# power_eagle_1.net
KiCad netlist of a schematic drawn in Altium Designer
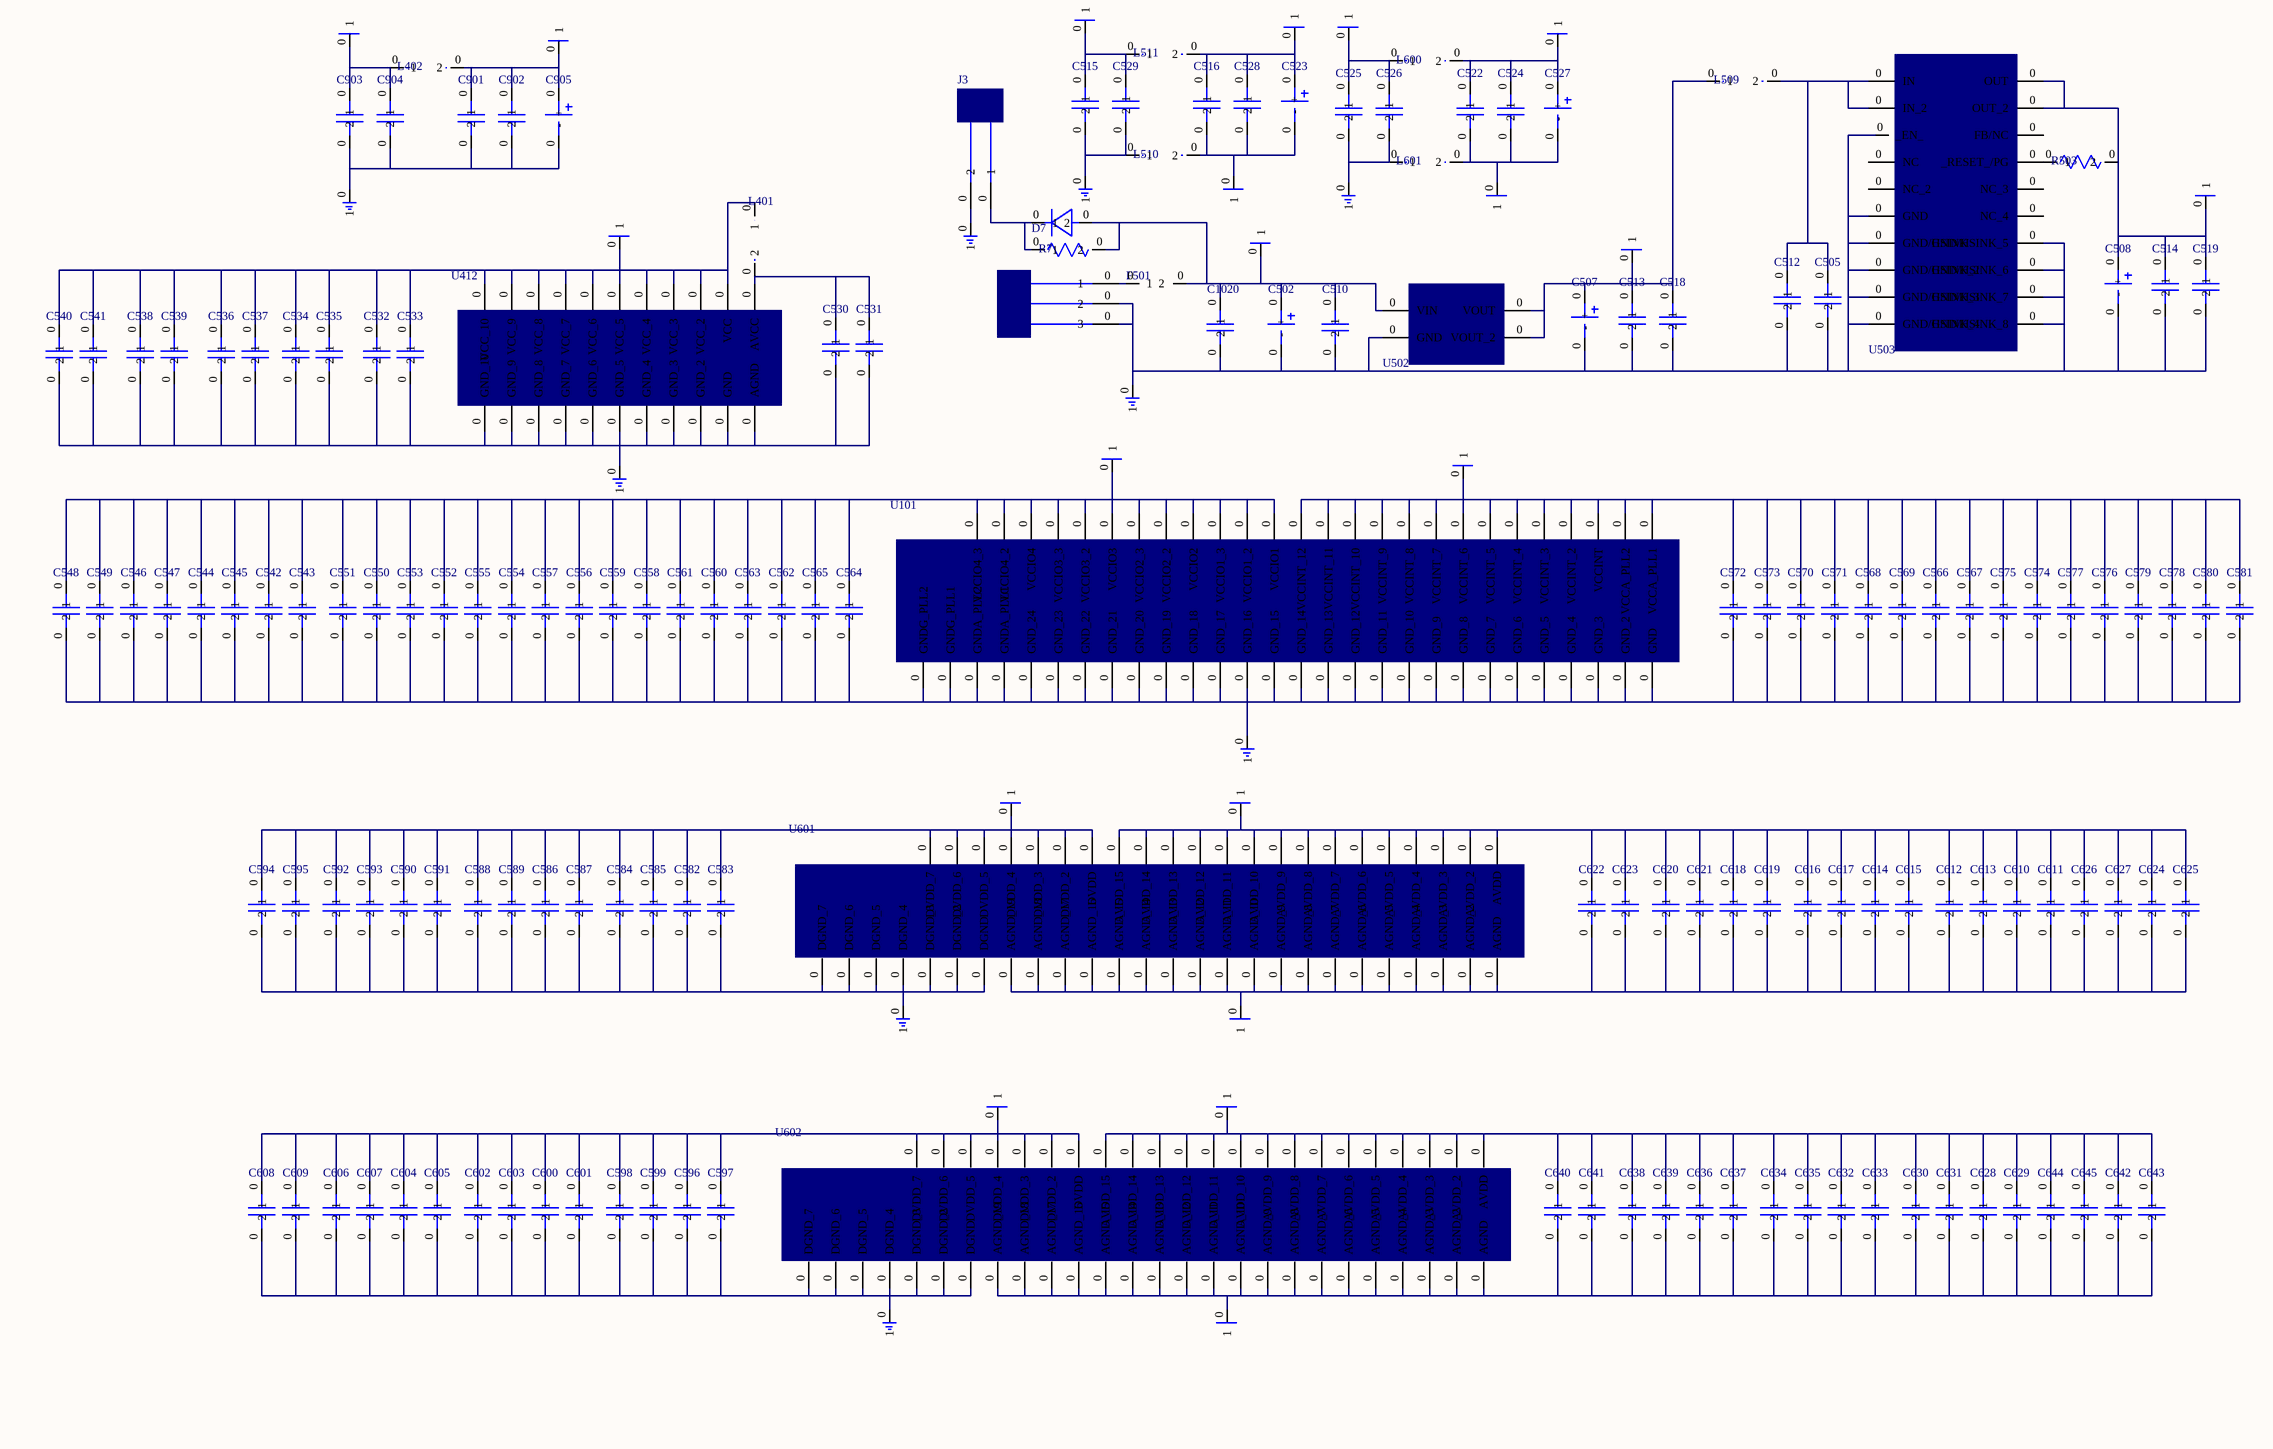
[diagram p0: power_eagle_1.SchDoc]

(export (version "E")
  (design (tool "Eeschema 10.0.6"))
  (components
    (comp (ref "C502") (value "~") (libsource (lib "") (part "CAPACITOR-2_5")))
    (comp (ref "C505") (value "~") (libsource (lib "") (part "CAPACITOR-1_84")))
    (comp (ref "C507") (value "~") (libsource (lib "") (part "CAPACITOR-2_4")))
    (comp (ref "C508") (value "~") (libsource (lib "") (part "CAPACITOR-2_3")))
    (comp (ref "C510") (value "~") (libsource (lib "") (part "CAPACITOR-1_63")))
    (comp (ref "C512") (value "~") (libsource (lib "") (part "CAPACITOR-1_24")))
    (comp (ref "C513") (value "~") (libsource (lib "") (part "CAPACITOR-1_2")))
    (comp (ref "C514") (value "~") (libsource (lib "") (part "CAPACITOR-1_52")))
    (comp (ref "C515") (value "~") (libsource (lib "") (part "CAPACITOR-1_101")))
    (comp (ref "C516") (value "~") (libsource (lib "") (part "CAPACITOR-1_31")))
    (comp (ref "C518") (value "~") (libsource (lib "") (part "CAPACITOR-1_33")))
    (comp (ref "C519") (value "~") (libsource (lib "") (part "CAPACITOR-1_108")))
    (comp (ref "C522") (value "~") (libsource (lib "") (part "CAPACITOR-1_9")))
    (comp (ref "C523") (value "~") (libsource (lib "openjson") (part "CAPACITOR-2")))
    (comp (ref "C524") (value "~") (libsource (lib "") (part "CAPACITOR-1_65")))
    (comp (ref "C525") (value "~") (libsource (lib "") (part "CAPACITOR-1_6")))
    (comp (ref "C526") (value "~") (libsource (lib "") (part "CAPACITOR-1_23")))
    (comp (ref "C527") (value "~") (libsource (lib "") (part "CAPACITOR-2_1")))
    (comp (ref "C528") (value "~") (libsource (lib "") (part "CAPACITOR-1_75")))
    (comp (ref "C529") (value "~") (libsource (lib "") (part "CAPACITOR-1_104")))
    (comp (ref "C530") (value "~") (libsource (lib "") (part "CAPACITOR-1_25")))
    (comp (ref "C531") (value "~") (libsource (lib "") (part "CAPACITOR-1_69")))
    (comp (ref "C532") (value "~") (libsource (lib "") (part "CAPACITOR-1_20")))
    (comp (ref "C533") (value "~") (libsource (lib "") (part "CAPACITOR-1_48")))
    (comp (ref "C534") (value "~") (libsource (lib "") (part "CAPACITOR-1_5")))
    (comp (ref "C535") (value "~") (libsource (lib "") (part "CAPACITOR-1_55")))
    (comp (ref "C536") (value "~") (libsource (lib "") (part "CAPACITOR-1_119")))
    (comp (ref "C537") (value "~") (libsource (lib "") (part "CAPACITOR-1_12")))
    (comp (ref "C538") (value "~") (libsource (lib "") (part "CAPACITOR-1_126")))
    (comp (ref "C539") (value "~") (libsource (lib "") (part "CAPACITOR-1_116")))
    (comp (ref "C540") (value "~") (libsource (lib "") (part "CAPACITOR-1_49")))
    (comp (ref "C541") (value "~") (libsource (lib "") (part "CAPACITOR-1_37")))
    (comp (ref "C542") (value "~") (libsource (lib "") (part "CAPACITOR-1_18")))
    (comp (ref "C543") (value "~") (libsource (lib "") (part "CAPACITOR-1_36")))
    (comp (ref "C544") (value "~") (libsource (lib "") (part "CAPACITOR-1_114")))
    (comp (ref "C545") (value "~") (libsource (lib "") (part "CAPACITOR-1_11")))
    (comp (ref "C546") (value "~") (libsource (lib "") (part "CAPACITOR-1_30")))
    (comp (ref "C547") (value "~") (libsource (lib "") (part "CAPACITOR-1_46")))
    (comp (ref "C548") (value "~") (libsource (lib "") (part "CAPACITOR-1_77")))
    (comp (ref "C549") (value "~") (libsource (lib "openjson") (part "CAPACITOR-1")))
    (comp (ref "C550") (value "~") (libsource (lib "") (part "CAPACITOR-1_62")))
    (comp (ref "C551") (value "~") (libsource (lib "") (part "CAPACITOR-1_68")))
    (comp (ref "C552") (value "~") (libsource (lib "") (part "CAPACITOR-1_56")))
    (comp (ref "C553") (value "~") (libsource (lib "") (part "CAPACITOR-1_38")))
    (comp (ref "C554") (value "~") (libsource (lib "") (part "CAPACITOR-1_3")))
    (comp (ref "C555") (value "~") (libsource (lib "") (part "CAPACITOR-1_35")))
    (comp (ref "C556") (value "~") (libsource (lib "") (part "CAPACITOR-1_100")))
    (comp (ref "C557") (value "~") (libsource (lib "") (part "CAPACITOR-1_39")))
    (comp (ref "C558") (value "~") (libsource (lib "") (part "CAPACITOR-1_113")))
    (comp (ref "C559") (value "~") (libsource (lib "") (part "CAPACITOR-1_15")))
    (comp (ref "C560") (value "~") (libsource (lib "") (part "CAPACITOR-1_121")))
    (comp (ref "C561") (value "~") (libsource (lib "") (part "CAPACITOR-1_81")))
    (comp (ref "C562") (value "~") (libsource (lib "") (part "CAPACITOR-1_72")))
    (comp (ref "C563") (value "~") (libsource (lib "") (part "CAPACITOR-1_134")))
    (comp (ref "C564") (value "~") (libsource (lib "") (part "CAPACITOR-1_40")))
    (comp (ref "C565") (value "~") (libsource (lib "") (part "CAPACITOR-1_27")))
    (comp (ref "C566") (value "~") (libsource (lib "") (part "CAPACITOR-1_32")))
    (comp (ref "C567") (value "~") (libsource (lib "") (part "CAPACITOR-1_127")))
    (comp (ref "C568") (value "~") (libsource (lib "") (part "CAPACITOR-1_79")))
    (comp (ref "C569") (value "~") (libsource (lib "") (part "CAPACITOR-1_13")))
    (comp (ref "C570") (value "~") (libsource (lib "") (part "CAPACITOR-1_91")))
    (comp (ref "C571") (value "~") (libsource (lib "") (part "CAPACITOR-1_21")))
    (comp (ref "C572") (value "~") (libsource (lib "") (part "CAPACITOR-1_45")))
    (comp (ref "C573") (value "~") (libsource (lib "") (part "CAPACITOR-1_53")))
    (comp (ref "C574") (value "~") (libsource (lib "") (part "CAPACITOR-1_132")))
    (comp (ref "C575") (value "~") (libsource (lib "") (part "CAPACITOR-1_7")))
    (comp (ref "C576") (value "~") (libsource (lib "") (part "CAPACITOR-1_64")))
    (comp (ref "C577") (value "~") (libsource (lib "") (part "CAPACITOR-1_42")))
    (comp (ref "C578") (value "~") (libsource (lib "") (part "CAPACITOR-1_125")))
    (comp (ref "C579") (value "~") (libsource (lib "") (part "CAPACITOR-1_123")))
    (comp (ref "C580") (value "~") (libsource (lib "") (part "CAPACITOR-1_58")))
    (comp (ref "C581") (value "~") (libsource (lib "") (part "CAPACITOR-1_26")))
    (comp (ref "C582") (value "~") (libsource (lib "") (part "CAPACITOR-1_1")))
    (comp (ref "C583") (value "~") (libsource (lib "") (part "CAPACITOR-1_83")))
    (comp (ref "C584") (value "~") (libsource (lib "") (part "CAPACITOR-1_51")))
    (comp (ref "C585") (value "~") (libsource (lib "") (part "CAPACITOR-1_57")))
    (comp (ref "C586") (value "~") (libsource (lib "") (part "CAPACITOR-1_131")))
    (comp (ref "C587") (value "~") (libsource (lib "") (part "CAPACITOR-1_105")))
    (comp (ref "C588") (value "~") (libsource (lib "") (part "CAPACITOR-1_115")))
    (comp (ref "C589") (value "~") (libsource (lib "") (part "CAPACITOR-1_130")))
    (comp (ref "C590") (value "~") (libsource (lib "") (part "CAPACITOR-1_120")))
    (comp (ref "C591") (value "~") (libsource (lib "") (part "CAPACITOR-1_86")))
    (comp (ref "C592") (value "~") (libsource (lib "") (part "CAPACITOR-1_112")))
    (comp (ref "C593") (value "~") (libsource (lib "") (part "CAPACITOR-1_22")))
    (comp (ref "C594") (value "~") (libsource (lib "") (part "CAPACITOR-1_67")))
    (comp (ref "C595") (value "~") (libsource (lib "") (part "CAPACITOR-1_133")))
    (comp (ref "C596") (value "~") (libsource (lib "") (part "CAPACITOR-1_80")))
    (comp (ref "C597") (value "~") (libsource (lib "") (part "CAPACITOR-1_28")))
    (comp (ref "C598") (value "~") (libsource (lib "") (part "CAPACITOR-1_118")))
    (comp (ref "C599") (value "~") (libsource (lib "") (part "CAPACITOR-1_54")))
    (comp (ref "C600") (value "~") (libsource (lib "") (part "CAPACITOR-1_66")))
    (comp (ref "C601") (value "~") (libsource (lib "") (part "CAPACITOR-1_76")))
    (comp (ref "C602") (value "~") (libsource (lib "") (part "CAPACITOR-1_74")))
    (comp (ref "C603") (value "~") (libsource (lib "") (part "CAPACITOR-1_89")))
    (comp (ref "C604") (value "~") (libsource (lib "") (part "CAPACITOR-1_90")))
    (comp (ref "C605") (value "~") (libsource (lib "") (part "CAPACITOR-1_59")))
    (comp (ref "C606") (value "~") (libsource (lib "") (part "CAPACITOR-1_117")))
    (comp (ref "C607") (value "~") (libsource (lib "") (part "CAPACITOR-1_34")))
    (comp (ref "C608") (value "~") (libsource (lib "") (part "CAPACITOR-1_71")))
    (comp (ref "C609") (value "~") (libsource (lib "") (part "CAPACITOR-1_88")))
    (comp (ref "C610") (value "~") (libsource (lib "") (part "CAPACITOR-1_17")))
    (comp (ref "C611") (value "~") (libsource (lib "") (part "CAPACITOR-1_16")))
    (comp (ref "C612") (value "~") (libsource (lib "") (part "CAPACITOR-1_19")))
    (comp (ref "C613") (value "~") (libsource (lib "") (part "CAPACITOR-1_44")))
    (comp (ref "C614") (value "~") (libsource (lib "") (part "CAPACITOR-1_103")))
    (comp (ref "C615") (value "~") (libsource (lib "") (part "CAPACITOR-1_110")))
    (comp (ref "C616") (value "~") (libsource (lib "") (part "CAPACITOR-1_97")))
    (comp (ref "C617") (value "~") (libsource (lib "") (part "CAPACITOR-1_73")))
    (comp (ref "C618") (value "~") (libsource (lib "") (part "CAPACITOR-1_96")))
    (comp (ref "C619") (value "~") (libsource (lib "") (part "CAPACITOR-1_41")))
    (comp (ref "C620") (value "~") (libsource (lib "") (part "CAPACITOR-1_128")))
    (comp (ref "C621") (value "~") (libsource (lib "") (part "CAPACITOR-1_61")))
    (comp (ref "C622") (value "~") (libsource (lib "") (part "CAPACITOR-1_10")))
    (comp (ref "C623") (value "~") (libsource (lib "") (part "CAPACITOR-1_50")))
    (comp (ref "C624") (value "~") (libsource (lib "") (part "CAPACITOR-1_85")))
    (comp (ref "C625") (value "~") (libsource (lib "") (part "CAPACITOR-1_43")))
    (comp (ref "C626") (value "~") (libsource (lib "") (part "CAPACITOR-1_47")))
    (comp (ref "C627") (value "~") (libsource (lib "") (part "CAPACITOR-1_99")))
    (comp (ref "C628") (value "~") (libsource (lib "") (part "CAPACITOR-1_94")))
    (comp (ref "C629") (value "~") (libsource (lib "") (part "CAPACITOR-1_78")))
    (comp (ref "C630") (value "~") (libsource (lib "") (part "CAPACITOR-1_129")))
    (comp (ref "C631") (value "~") (libsource (lib "") (part "CAPACITOR-1_111")))
    (comp (ref "C632") (value "~") (libsource (lib "") (part "CAPACITOR-1_109")))
    (comp (ref "C633") (value "~") (libsource (lib "") (part "CAPACITOR-1_60")))
    (comp (ref "C634") (value "~") (libsource (lib "") (part "CAPACITOR-1_14")))
    (comp (ref "C635") (value "~") (libsource (lib "") (part "CAPACITOR-1_8")))
    (comp (ref "C636") (value "~") (libsource (lib "") (part "CAPACITOR-1_135")))
    (comp (ref "C637") (value "~") (libsource (lib "") (part "CAPACITOR-1_93")))
    (comp (ref "C638") (value "~") (libsource (lib "") (part "CAPACITOR-1_122")))
    (comp (ref "C639") (value "~") (libsource (lib "") (part "CAPACITOR-1_82")))
    (comp (ref "C640") (value "~") (libsource (lib "") (part "CAPACITOR-1_4")))
    (comp (ref "C641") (value "~") (libsource (lib "") (part "CAPACITOR-1_107")))
    (comp (ref "C642") (value "~") (libsource (lib "") (part "CAPACITOR-1_102")))
    (comp (ref "C643") (value "~") (libsource (lib "") (part "CAPACITOR-1_95")))
    (comp (ref "C644") (value "~") (libsource (lib "") (part "CAPACITOR-1_92")))
    (comp (ref "C645") (value "~") (libsource (lib "") (part "CAPACITOR-1_70")))
    (comp (ref "C901") (value "~") (libsource (lib "") (part "CAPACITOR-1_87")))
    (comp (ref "C902") (value "~") (libsource (lib "") (part "CAPACITOR-1_29")))
    (comp (ref "C903") (value "~") (libsource (lib "") (part "CAPACITOR-1_106")))
    (comp (ref "C904") (value "~") (libsource (lib "") (part "CAPACITOR-1_124")))
    (comp (ref "C905") (value "~") (libsource (lib "") (part "CAPACITOR-2_2")))
    (comp (ref "C1020") (value "~") (libsource (lib "") (part "CAPACITOR-1_98")))
    (comp (ref "D7") (value "~") (libsource (lib "openjson") (part "DIODE-3")))
    (comp (ref "F501") (value "~") (libsource (lib "openjson") (part "FUSE-1")))
    (comp (ref "GENERIC-POWER") (value "~") (libsource (lib "openjson") (part "GENERIC-POWER")))
    (comp (ref "GENERIC-POWER-0") (value "~") (libsource (lib "openjson") (part "GENERIC-POWER")))
    (comp (ref "GENERIC-POWER-1") (value "~") (libsource (lib "openjson") (part "GENERIC-POWER")))
    (comp (ref "GENERIC-POWER-2") (value "~") (libsource (lib "openjson") (part "GENERIC-POWER")))
    (comp (ref "GENERIC-POWER-3") (value "~") (libsource (lib "openjson") (part "GENERIC-POWER")))
    (comp (ref "GENERIC-POWER-4") (value "~") (libsource (lib "") (part "GENERIC-POWER_1")))
    (comp (ref "GENERIC-POWER-6") (value "~") (libsource (lib "openjson") (part "GENERIC-POWER")))
    (comp (ref "GENERIC-POWER-7") (value "~") (libsource (lib "openjson") (part "GENERIC-POWER")))
    (comp (ref "GENERIC-POWER-8") (value "~") (libsource (lib "") (part "GENERIC-POWER_1")))
    (comp (ref "GENERIC-POWER-11") (value "~") (libsource (lib "openjson") (part "GENERIC-POWER")))
    (comp (ref "GENERIC-POWER-12") (value "~") (libsource (lib "openjson") (part "GENERIC-POWER")))
    (comp (ref "GENERIC-POWER-14") (value "~") (libsource (lib "openjson") (part "GENERIC-POWER")))
    (comp (ref "GENERIC-POWER-16") (value "~") (libsource (lib "openjson") (part "GENERIC-POWER")))
    (comp (ref "GENERIC-POWER-17") (value "~") (libsource (lib "openjson") (part "GENERIC-POWER")))
    (comp (ref "GENERIC-POWER-18") (value "~") (libsource (lib "") (part "GENERIC-POWER_1")))
    (comp (ref "GENERIC-POWER-20") (value "~") (libsource (lib "openjson") (part "GENERIC-POWER")))
    (comp (ref "GENERIC-POWER-21") (value "~") (libsource (lib "openjson") (part "GENERIC-POWER")))
    (comp (ref "GENERIC-POWER-22") (value "~") (libsource (lib "") (part "GENERIC-POWER_1")))
    (comp (ref "GENERIC-POWER-23") (value "~") (libsource (lib "openjson") (part "GENERIC-POWER")))
    (comp (ref "GENERIC-POWER-24") (value "~") (libsource (lib "openjson") (part "GENERIC-POWER")))
    (comp (ref "GND-1") (value "~") (libsource (lib "openjson") (part "GND-1")))
    (comp (ref "GND-1-5") (value "~") (libsource (lib "openjson") (part "GND-1")))
    (comp (ref "GND-1-9") (value "~") (libsource (lib "openjson") (part "GND-1")))
    (comp (ref "GND-1-10") (value "~") (libsource (lib "openjson") (part "GND-1")))
    (comp (ref "GND-1-13") (value "~") (libsource (lib "openjson") (part "GND-1")))
    (comp (ref "GND-1-15") (value "~") (libsource (lib "openjson") (part "GND-1")))
    (comp (ref "GND-1-19") (value "~") (libsource (lib "openjson") (part "GND-1")))
    (comp (ref "GND-1-25") (value "~") (libsource (lib "openjson") (part "GND-1")))
    (comp (ref "GND-1-26") (value "~") (libsource (lib "openjson") (part "GND-1")))
    (comp (ref "J3") (value "~") (libsource (lib "openjson") (part "CONNECTOR2-1")))
    (comp (ref "J502") (value "~") (libsource (lib "openjson") (part "CONNECTOR3-1")))
    (comp (ref "L401") (value "~") (libsource (lib "") (part "INDUCTOR-1_3")))
    (comp (ref "L402") (value "~") (libsource (lib "") (part "INDUCTOR-1_1")))
    (comp (ref "L509") (value "~") (libsource (lib "") (part "INDUCTOR-1_4")))
    (comp (ref "L510") (value "~") (libsource (lib "") (part "INDUCTOR-1_6")))
    (comp (ref "L511") (value "~") (libsource (lib "") (part "INDUCTOR-1_5")))
    (comp (ref "L600") (value "~") (libsource (lib "openjson") (part "INDUCTOR-1")))
    (comp (ref "L601") (value "~") (libsource (lib "") (part "INDUCTOR-1_2")))
    (comp (ref "R7") (value "~") (libsource (lib "") (part "RESISTOR-1_1")))
    (comp (ref "R503") (value "~") (libsource (lib "openjson") (part "RESISTOR-1")))
    (comp (ref "U101") (value "~") (libsource (lib "openjson") (part "EP1C12-PQ240-PWR")))
    (comp (ref "U412") (value "~") (libsource (lib "openjson") (part "CY7C68013-TQ100-PWR")))
    (comp (ref "U502") (value "~") (libsource (lib "openjson") (part "LT1085")))
    (comp (ref "U503") (value "~") (libsource (lib "openjson") (part "TPS777XX-PWP")))
    (comp (ref "U601") (value "~") (libsource (lib "") (part "AD986X-PWR_1")))
    (comp (ref "U602") (value "~") (libsource (lib "openjson") (part "AD986X-PWR")))
  )
  (nets
    (net (code "1") (name "Net-(C505-1)") (class "Default")
      (node (ref "C505") (pin "0") (pinfunction "1_0") (pintype "passive"))
      (node (ref "C512") (pin "0") (pinfunction "1_0") (pintype "passive"))
      (node (ref "L509") (pin "0") (pinfunction "2_0") (pintype "passive"))
      (node (ref "U503") (pin "0") (pinfunction "IN_0") (pintype "passive"))
    )
    (net (code "2") (name "Net-(C507-+)") (class "Default")
      (node (ref "C507") (pin "0") (pinfunction "+_0") (pintype "passive"))
      (node (ref "C513") (pin "0") (pinfunction "1_0") (pintype "passive"))
      (node (ref "C518") (pin "0") (pinfunction "1_0") (pintype "passive"))
      (node (ref "GENERIC-POWER-1") (pin "0") (pinfunction "1_0") (pintype "passive"))
      (node (ref "L509") (pin "0") (pinfunction "1_0") (pintype "passive"))
      (node (ref "U502") (pin "0") (pinfunction "VOUT_0") (pintype "passive"))
    )
    (net (code "3") (name "Net-(C508-+)") (class "Default")
      (node (ref "C508") (pin "0") (pinfunction "+_0") (pintype "passive"))
      (node (ref "C514") (pin "0") (pinfunction "1_0") (pintype "passive"))
      (node (ref "C519") (pin "0") (pinfunction "1_0") (pintype "passive"))
      (node (ref "GENERIC-POWER") (pin "0") (pinfunction "1_0") (pintype "passive"))
      (node (ref "R503") (pin "0") (pinfunction "2_0") (pintype "passive"))
      (node (ref "U503") (pin "0") (pinfunction "OUT_0") (pintype "passive"))
    )
    (net (code "4") (name "Net-(C515-1)") (class "Default")
      (node (ref "C515") (pin "0") (pinfunction "1_0") (pintype "passive"))
      (node (ref "C529") (pin "0") (pinfunction "1_0") (pintype "passive"))
      (node (ref "GENERIC-POWER-6") (pin "0") (pinfunction "1_0") (pintype "passive"))
      (node (ref "L511") (pin "0") (pinfunction "1_0") (pintype "passive"))
    )
    (net (code "5") (name "Net-(C515-2)") (class "Default")
      (node (ref "C515") (pin "0") (pinfunction "2_0") (pintype "passive"))
      (node (ref "C529") (pin "0") (pinfunction "2_0") (pintype "passive"))
      (node (ref "GND-1-9") (pin "0") (pinfunction "1_0") (pintype "passive"))
      (node (ref "L510") (pin "0") (pinfunction "1_0") (pintype "passive"))
    )
    (net (code "6") (name "Net-(C516-1)") (class "Default")
      (node (ref "C516") (pin "0") (pinfunction "1_0") (pintype "passive"))
      (node (ref "C523") (pin "0") (pinfunction "+_0") (pintype "passive"))
      (node (ref "C528") (pin "0") (pinfunction "1_0") (pintype "passive"))
      (node (ref "GENERIC-POWER-7") (pin "0") (pinfunction "1_0") (pintype "passive"))
      (node (ref "L511") (pin "0") (pinfunction "2_0") (pintype "passive"))
    )
    (net (code "7") (name "Net-(C516-2)") (class "Default")
      (node (ref "C516") (pin "0") (pinfunction "2_0") (pintype "passive"))
      (node (ref "C523") (pin "0") (pinfunction "-_0") (pintype "passive"))
      (node (ref "C528") (pin "0") (pinfunction "2_0") (pintype "passive"))
      (node (ref "GENERIC-POWER-8") (pin "0") (pinfunction "1_0") (pintype "passive"))
      (node (ref "L510") (pin "0") (pinfunction "2_0") (pintype "passive"))
    )
    (net (code "8") (name "Net-(C522-1)") (class "Default")
      (node (ref "C522") (pin "0") (pinfunction "1_0") (pintype "passive"))
      (node (ref "C524") (pin "0") (pinfunction "1_0") (pintype "passive"))
      (node (ref "C527") (pin "0") (pinfunction "+_0") (pintype "passive"))
      (node (ref "GENERIC-POWER-3") (pin "0") (pinfunction "1_0") (pintype "passive"))
      (node (ref "L600") (pin "0") (pinfunction "2_0") (pintype "passive"))
    )
    (net (code "9") (name "Net-(C522-2)") (class "Default")
      (node (ref "C522") (pin "0") (pinfunction "2_0") (pintype "passive"))
      (node (ref "C524") (pin "0") (pinfunction "2_0") (pintype "passive"))
      (node (ref "C527") (pin "0") (pinfunction "-_0") (pintype "passive"))
      (node (ref "GENERIC-POWER-4") (pin "0") (pinfunction "1_0") (pintype "passive"))
      (node (ref "L601") (pin "0") (pinfunction "2_0") (pintype "passive"))
    )
    (net (code "10") (name "Net-(C525-1)") (class "Default")
      (node (ref "C525") (pin "0") (pinfunction "1_0") (pintype "passive"))
      (node (ref "C526") (pin "0") (pinfunction "1_0") (pintype "passive"))
      (node (ref "GENERIC-POWER-2") (pin "0") (pinfunction "1_0") (pintype "passive"))
      (node (ref "L600") (pin "0") (pinfunction "1_0") (pintype "passive"))
    )
    (net (code "11") (name "Net-(C525-2)") (class "Default")
      (node (ref "C525") (pin "0") (pinfunction "2_0") (pintype "passive"))
      (node (ref "C526") (pin "0") (pinfunction "2_0") (pintype "passive"))
      (node (ref "GND-1-5") (pin "0") (pinfunction "1_0") (pintype "passive"))
      (node (ref "L601") (pin "0") (pinfunction "1_0") (pintype "passive"))
    )
    (net (code "12") (name "Net-(C530-1)") (class "Default")
      (node (ref "C530") (pin "0") (pinfunction "1_0") (pintype "passive"))
      (node (ref "C531") (pin "0") (pinfunction "1_0") (pintype "passive"))
      (node (ref "L401") (pin "0") (pinfunction "2_0") (pintype "passive"))
      (node (ref "U412") (pin "0") (pinfunction "AVCC_0") (pintype "passive"))
    )
    (net (code "13") (name "Net-(C530-2)") (class "Default")
      (node (ref "C530") (pin "0") (pinfunction "2_0") (pintype "passive"))
      (node (ref "C531") (pin "0") (pinfunction "2_0") (pintype "passive"))
      (node (ref "C532") (pin "0") (pinfunction "2_0") (pintype "passive"))
      (node (ref "C533") (pin "0") (pinfunction "2_0") (pintype "passive"))
      (node (ref "C534") (pin "0") (pinfunction "2_0") (pintype "passive"))
      (node (ref "C535") (pin "0") (pinfunction "2_0") (pintype "passive"))
      (node (ref "C536") (pin "0") (pinfunction "2_0") (pintype "passive"))
      (node (ref "C537") (pin "0") (pinfunction "2_0") (pintype "passive"))
      (node (ref "C538") (pin "0") (pinfunction "2_0") (pintype "passive"))
      (node (ref "C539") (pin "0") (pinfunction "2_0") (pintype "passive"))
      (node (ref "C540") (pin "0") (pinfunction "2_0") (pintype "passive"))
      (node (ref "C541") (pin "0") (pinfunction "2_0") (pintype "passive"))
      (node (ref "GND-1-10") (pin "0") (pinfunction "1_0") (pintype "passive"))
      (node (ref "U412") (pin "0") (pinfunction "AGND_0") (pintype "passive"))
    )
    (net (code "14") (name "Net-(C532-1)") (class "Default")
      (node (ref "C532") (pin "0") (pinfunction "1_0") (pintype "passive"))
      (node (ref "C533") (pin "0") (pinfunction "1_0") (pintype "passive"))
      (node (ref "C534") (pin "0") (pinfunction "1_0") (pintype "passive"))
      (node (ref "C535") (pin "0") (pinfunction "1_0") (pintype "passive"))
      (node (ref "C536") (pin "0") (pinfunction "1_0") (pintype "passive"))
      (node (ref "C537") (pin "0") (pinfunction "1_0") (pintype "passive"))
      (node (ref "C538") (pin "0") (pinfunction "1_0") (pintype "passive"))
      (node (ref "C539") (pin "0") (pinfunction "1_0") (pintype "passive"))
      (node (ref "C540") (pin "0") (pinfunction "1_0") (pintype "passive"))
      (node (ref "C541") (pin "0") (pinfunction "1_0") (pintype "passive"))
      (node (ref "GENERIC-POWER-11") (pin "0") (pinfunction "1_0") (pintype "passive"))
      (node (ref "L401") (pin "0") (pinfunction "1_0") (pintype "passive"))
      (node (ref "U412") (pin "0") (pinfunction "VCC_3_0") (pintype "passive"))
    )
    (net (code "15") (name "Net-(C542-1)") (class "Default")
      (node (ref "C542") (pin "0") (pinfunction "1_0") (pintype "passive"))
      (node (ref "C543") (pin "0") (pinfunction "1_0") (pintype "passive"))
      (node (ref "C544") (pin "0") (pinfunction "1_0") (pintype "passive"))
      (node (ref "C545") (pin "0") (pinfunction "1_0") (pintype "passive"))
      (node (ref "C546") (pin "0") (pinfunction "1_0") (pintype "passive"))
      (node (ref "C547") (pin "0") (pinfunction "1_0") (pintype "passive"))
      (node (ref "C548") (pin "0") (pinfunction "1_0") (pintype "passive"))
      (node (ref "C549") (pin "0") (pinfunction "1_0") (pintype "passive"))
      (node (ref "C550") (pin "0") (pinfunction "1_0") (pintype "passive"))
      (node (ref "C551") (pin "0") (pinfunction "1_0") (pintype "passive"))
      (node (ref "C552") (pin "0") (pinfunction "1_0") (pintype "passive"))
      (node (ref "C553") (pin "0") (pinfunction "1_0") (pintype "passive"))
      (node (ref "C554") (pin "0") (pinfunction "1_0") (pintype "passive"))
      (node (ref "C555") (pin "0") (pinfunction "1_0") (pintype "passive"))
      (node (ref "C556") (pin "0") (pinfunction "1_0") (pintype "passive"))
      (node (ref "C557") (pin "0") (pinfunction "1_0") (pintype "passive"))
      (node (ref "C558") (pin "0") (pinfunction "1_0") (pintype "passive"))
      (node (ref "C559") (pin "0") (pinfunction "1_0") (pintype "passive"))
      (node (ref "C560") (pin "0") (pinfunction "1_0") (pintype "passive"))
      (node (ref "C561") (pin "0") (pinfunction "1_0") (pintype "passive"))
      (node (ref "C562") (pin "0") (pinfunction "1_0") (pintype "passive"))
      (node (ref "C563") (pin "0") (pinfunction "1_0") (pintype "passive"))
      (node (ref "C564") (pin "0") (pinfunction "1_0") (pintype "passive"))
      (node (ref "C565") (pin "0") (pinfunction "1_0") (pintype "passive"))
      (node (ref "GENERIC-POWER-14") (pin "0") (pinfunction "1_0") (pintype "passive"))
      (node (ref "U101") (pin "0") (pinfunction "VCCIO1_2_0") (pintype "passive"))
    )
    (net (code "16") (name "Net-(C542-2)") (class "Default")
      (node (ref "C542") (pin "0") (pinfunction "2_0") (pintype "passive"))
      (node (ref "C543") (pin "0") (pinfunction "2_0") (pintype "passive"))
      (node (ref "C544") (pin "0") (pinfunction "2_0") (pintype "passive"))
      (node (ref "C545") (pin "0") (pinfunction "2_0") (pintype "passive"))
      (node (ref "C546") (pin "0") (pinfunction "2_0") (pintype "passive"))
      (node (ref "C547") (pin "0") (pinfunction "2_0") (pintype "passive"))
      (node (ref "C548") (pin "0") (pinfunction "2_0") (pintype "passive"))
      (node (ref "C549") (pin "0") (pinfunction "2_0") (pintype "passive"))
      (node (ref "C550") (pin "0") (pinfunction "2_0") (pintype "passive"))
      (node (ref "C551") (pin "0") (pinfunction "2_0") (pintype "passive"))
      (node (ref "C552") (pin "0") (pinfunction "2_0") (pintype "passive"))
      (node (ref "C553") (pin "0") (pinfunction "2_0") (pintype "passive"))
      (node (ref "C554") (pin "0") (pinfunction "2_0") (pintype "passive"))
      (node (ref "C555") (pin "0") (pinfunction "2_0") (pintype "passive"))
      (node (ref "C556") (pin "0") (pinfunction "2_0") (pintype "passive"))
      (node (ref "C557") (pin "0") (pinfunction "2_0") (pintype "passive"))
      (node (ref "C558") (pin "0") (pinfunction "2_0") (pintype "passive"))
      (node (ref "C559") (pin "0") (pinfunction "2_0") (pintype "passive"))
      (node (ref "C560") (pin "0") (pinfunction "2_0") (pintype "passive"))
      (node (ref "C561") (pin "0") (pinfunction "2_0") (pintype "passive"))
      (node (ref "C562") (pin "0") (pinfunction "2_0") (pintype "passive"))
      (node (ref "C563") (pin "0") (pinfunction "2_0") (pintype "passive"))
      (node (ref "C564") (pin "0") (pinfunction "2_0") (pintype "passive"))
      (node (ref "C565") (pin "0") (pinfunction "2_0") (pintype "passive"))
      (node (ref "C566") (pin "0") (pinfunction "2_0") (pintype "passive"))
      (node (ref "C567") (pin "0") (pinfunction "2_0") (pintype "passive"))
      (node (ref "C568") (pin "0") (pinfunction "2_0") (pintype "passive"))
      (node (ref "C569") (pin "0") (pinfunction "2_0") (pintype "passive"))
      (node (ref "C570") (pin "0") (pinfunction "2_0") (pintype "passive"))
      (node (ref "C571") (pin "0") (pinfunction "2_0") (pintype "passive"))
      (node (ref "C572") (pin "0") (pinfunction "2_0") (pintype "passive"))
      (node (ref "C573") (pin "0") (pinfunction "2_0") (pintype "passive"))
      (node (ref "C574") (pin "0") (pinfunction "2_0") (pintype "passive"))
      (node (ref "C575") (pin "0") (pinfunction "2_0") (pintype "passive"))
      (node (ref "C576") (pin "0") (pinfunction "2_0") (pintype "passive"))
      (node (ref "C577") (pin "0") (pinfunction "2_0") (pintype "passive"))
      (node (ref "C578") (pin "0") (pinfunction "2_0") (pintype "passive"))
      (node (ref "C579") (pin "0") (pinfunction "2_0") (pintype "passive"))
      (node (ref "C580") (pin "0") (pinfunction "2_0") (pintype "passive"))
      (node (ref "C581") (pin "0") (pinfunction "2_0") (pintype "passive"))
      (node (ref "GND-1-13") (pin "0") (pinfunction "1_0") (pintype "passive"))
      (node (ref "U101") (pin "0") (pinfunction "GND_15_0") (pintype "passive"))
    )
    (net (code "17") (name "Net-(C566-1)") (class "Default")
      (node (ref "C566") (pin "0") (pinfunction "1_0") (pintype "passive"))
      (node (ref "C567") (pin "0") (pinfunction "1_0") (pintype "passive"))
      (node (ref "C568") (pin "0") (pinfunction "1_0") (pintype "passive"))
      (node (ref "C569") (pin "0") (pinfunction "1_0") (pintype "passive"))
      (node (ref "C570") (pin "0") (pinfunction "1_0") (pintype "passive"))
      (node (ref "C571") (pin "0") (pinfunction "1_0") (pintype "passive"))
      (node (ref "C572") (pin "0") (pinfunction "1_0") (pintype "passive"))
      (node (ref "C573") (pin "0") (pinfunction "1_0") (pintype "passive"))
      (node (ref "C574") (pin "0") (pinfunction "1_0") (pintype "passive"))
      (node (ref "C575") (pin "0") (pinfunction "1_0") (pintype "passive"))
      (node (ref "C576") (pin "0") (pinfunction "1_0") (pintype "passive"))
      (node (ref "C577") (pin "0") (pinfunction "1_0") (pintype "passive"))
      (node (ref "C578") (pin "0") (pinfunction "1_0") (pintype "passive"))
      (node (ref "C579") (pin "0") (pinfunction "1_0") (pintype "passive"))
      (node (ref "C580") (pin "0") (pinfunction "1_0") (pintype "passive"))
      (node (ref "C581") (pin "0") (pinfunction "1_0") (pintype "passive"))
      (node (ref "GENERIC-POWER-12") (pin "0") (pinfunction "1_0") (pintype "passive"))
      (node (ref "U101") (pin "0") (pinfunction "VCCA_PLL2_0") (pintype "passive"))
    )
    (net (code "18") (name "Net-(C582-1)") (class "Default")
      (node (ref "C582") (pin "0") (pinfunction "1_0") (pintype "passive"))
      (node (ref "C583") (pin "0") (pinfunction "1_0") (pintype "passive"))
      (node (ref "C584") (pin "0") (pinfunction "1_0") (pintype "passive"))
      (node (ref "C585") (pin "0") (pinfunction "1_0") (pintype "passive"))
      (node (ref "C586") (pin "0") (pinfunction "1_0") (pintype "passive"))
      (node (ref "C587") (pin "0") (pinfunction "1_0") (pintype "passive"))
      (node (ref "C588") (pin "0") (pinfunction "1_0") (pintype "passive"))
      (node (ref "C589") (pin "0") (pinfunction "1_0") (pintype "passive"))
      (node (ref "C590") (pin "0") (pinfunction "1_0") (pintype "passive"))
      (node (ref "C591") (pin "0") (pinfunction "1_0") (pintype "passive"))
      (node (ref "C592") (pin "0") (pinfunction "1_0") (pintype "passive"))
      (node (ref "C593") (pin "0") (pinfunction "1_0") (pintype "passive"))
      (node (ref "C594") (pin "0") (pinfunction "1_0") (pintype "passive"))
      (node (ref "C595") (pin "0") (pinfunction "1_0") (pintype "passive"))
      (node (ref "GENERIC-POWER-17") (pin "0") (pinfunction "1_0") (pintype "passive"))
      (node (ref "U601") (pin "0") (pinfunction "DVDD_0") (pintype "passive"))
    )
    (net (code "19") (name "Net-(C582-2)") (class "Default")
      (node (ref "C582") (pin "0") (pinfunction "2_0") (pintype "passive"))
      (node (ref "C583") (pin "0") (pinfunction "2_0") (pintype "passive"))
      (node (ref "C584") (pin "0") (pinfunction "2_0") (pintype "passive"))
      (node (ref "C585") (pin "0") (pinfunction "2_0") (pintype "passive"))
      (node (ref "C586") (pin "0") (pinfunction "2_0") (pintype "passive"))
      (node (ref "C587") (pin "0") (pinfunction "2_0") (pintype "passive"))
      (node (ref "C588") (pin "0") (pinfunction "2_0") (pintype "passive"))
      (node (ref "C589") (pin "0") (pinfunction "2_0") (pintype "passive"))
      (node (ref "C590") (pin "0") (pinfunction "2_0") (pintype "passive"))
      (node (ref "C591") (pin "0") (pinfunction "2_0") (pintype "passive"))
      (node (ref "C592") (pin "0") (pinfunction "2_0") (pintype "passive"))
      (node (ref "C593") (pin "0") (pinfunction "2_0") (pintype "passive"))
      (node (ref "C594") (pin "0") (pinfunction "2_0") (pintype "passive"))
      (node (ref "C595") (pin "0") (pinfunction "2_0") (pintype "passive"))
      (node (ref "GND-1-15") (pin "0") (pinfunction "1_0") (pintype "passive"))
      (node (ref "U601") (pin "0") (pinfunction "DGND_0") (pintype "passive"))
    )
    (net (code "20") (name "Net-(C596-1)") (class "Default")
      (node (ref "C596") (pin "0") (pinfunction "1_0") (pintype "passive"))
      (node (ref "C597") (pin "0") (pinfunction "1_0") (pintype "passive"))
      (node (ref "C598") (pin "0") (pinfunction "1_0") (pintype "passive"))
      (node (ref "C599") (pin "0") (pinfunction "1_0") (pintype "passive"))
      (node (ref "C600") (pin "0") (pinfunction "1_0") (pintype "passive"))
      (node (ref "C601") (pin "0") (pinfunction "1_0") (pintype "passive"))
      (node (ref "C602") (pin "0") (pinfunction "1_0") (pintype "passive"))
      (node (ref "C603") (pin "0") (pinfunction "1_0") (pintype "passive"))
      (node (ref "C604") (pin "0") (pinfunction "1_0") (pintype "passive"))
      (node (ref "C605") (pin "0") (pinfunction "1_0") (pintype "passive"))
      (node (ref "C606") (pin "0") (pinfunction "1_0") (pintype "passive"))
      (node (ref "C607") (pin "0") (pinfunction "1_0") (pintype "passive"))
      (node (ref "C608") (pin "0") (pinfunction "1_0") (pintype "passive"))
      (node (ref "C609") (pin "0") (pinfunction "1_0") (pintype "passive"))
      (node (ref "GENERIC-POWER-21") (pin "0") (pinfunction "1_0") (pintype "passive"))
      (node (ref "U602") (pin "0") (pinfunction "DVDD_0") (pintype "passive"))
    )
    (net (code "21") (name "Net-(C596-2)") (class "Default")
      (node (ref "C596") (pin "0") (pinfunction "2_0") (pintype "passive"))
      (node (ref "C597") (pin "0") (pinfunction "2_0") (pintype "passive"))
      (node (ref "C598") (pin "0") (pinfunction "2_0") (pintype "passive"))
      (node (ref "C599") (pin "0") (pinfunction "2_0") (pintype "passive"))
      (node (ref "C600") (pin "0") (pinfunction "2_0") (pintype "passive"))
      (node (ref "C601") (pin "0") (pinfunction "2_0") (pintype "passive"))
      (node (ref "C602") (pin "0") (pinfunction "2_0") (pintype "passive"))
      (node (ref "C603") (pin "0") (pinfunction "2_0") (pintype "passive"))
      (node (ref "C604") (pin "0") (pinfunction "2_0") (pintype "passive"))
      (node (ref "C605") (pin "0") (pinfunction "2_0") (pintype "passive"))
      (node (ref "C606") (pin "0") (pinfunction "2_0") (pintype "passive"))
      (node (ref "C607") (pin "0") (pinfunction "2_0") (pintype "passive"))
      (node (ref "C608") (pin "0") (pinfunction "2_0") (pintype "passive"))
      (node (ref "C609") (pin "0") (pinfunction "2_0") (pintype "passive"))
      (node (ref "GND-1-19") (pin "0") (pinfunction "1_0") (pintype "passive"))
      (node (ref "U602") (pin "0") (pinfunction "DGND_0") (pintype "passive"))
    )
    (net (code "22") (name "Net-(C610-1)") (class "Default")
      (node (ref "C610") (pin "0") (pinfunction "1_0") (pintype "passive"))
      (node (ref "C611") (pin "0") (pinfunction "1_0") (pintype "passive"))
      (node (ref "C612") (pin "0") (pinfunction "1_0") (pintype "passive"))
      (node (ref "C613") (pin "0") (pinfunction "1_0") (pintype "passive"))
      (node (ref "C614") (pin "0") (pinfunction "1_0") (pintype "passive"))
      (node (ref "C615") (pin "0") (pinfunction "1_0") (pintype "passive"))
      (node (ref "C616") (pin "0") (pinfunction "1_0") (pintype "passive"))
      (node (ref "C617") (pin "0") (pinfunction "1_0") (pintype "passive"))
      (node (ref "C618") (pin "0") (pinfunction "1_0") (pintype "passive"))
      (node (ref "C619") (pin "0") (pinfunction "1_0") (pintype "passive"))
      (node (ref "C620") (pin "0") (pinfunction "1_0") (pintype "passive"))
      (node (ref "C621") (pin "0") (pinfunction "1_0") (pintype "passive"))
      (node (ref "C622") (pin "0") (pinfunction "1_0") (pintype "passive"))
      (node (ref "C623") (pin "0") (pinfunction "1_0") (pintype "passive"))
      (node (ref "C624") (pin "0") (pinfunction "1_0") (pintype "passive"))
      (node (ref "C625") (pin "0") (pinfunction "1_0") (pintype "passive"))
      (node (ref "C626") (pin "0") (pinfunction "1_0") (pintype "passive"))
      (node (ref "C627") (pin "0") (pinfunction "1_0") (pintype "passive"))
      (node (ref "GENERIC-POWER-16") (pin "0") (pinfunction "1_0") (pintype "passive"))
      (node (ref "U601") (pin "0") (pinfunction "AVDD_2_0") (pintype "passive"))
    )
    (net (code "23") (name "Net-(C610-2)") (class "Default")
      (node (ref "C610") (pin "0") (pinfunction "2_0") (pintype "passive"))
      (node (ref "C611") (pin "0") (pinfunction "2_0") (pintype "passive"))
      (node (ref "C612") (pin "0") (pinfunction "2_0") (pintype "passive"))
      (node (ref "C613") (pin "0") (pinfunction "2_0") (pintype "passive"))
      (node (ref "C614") (pin "0") (pinfunction "2_0") (pintype "passive"))
      (node (ref "C615") (pin "0") (pinfunction "2_0") (pintype "passive"))
      (node (ref "C616") (pin "0") (pinfunction "2_0") (pintype "passive"))
      (node (ref "C617") (pin "0") (pinfunction "2_0") (pintype "passive"))
      (node (ref "C618") (pin "0") (pinfunction "2_0") (pintype "passive"))
      (node (ref "C619") (pin "0") (pinfunction "2_0") (pintype "passive"))
      (node (ref "C620") (pin "0") (pinfunction "2_0") (pintype "passive"))
      (node (ref "C621") (pin "0") (pinfunction "2_0") (pintype "passive"))
      (node (ref "C622") (pin "0") (pinfunction "2_0") (pintype "passive"))
      (node (ref "C623") (pin "0") (pinfunction "2_0") (pintype "passive"))
      (node (ref "C624") (pin "0") (pinfunction "2_0") (pintype "passive"))
      (node (ref "C625") (pin "0") (pinfunction "2_0") (pintype "passive"))
      (node (ref "C626") (pin "0") (pinfunction "2_0") (pintype "passive"))
      (node (ref "C627") (pin "0") (pinfunction "2_0") (pintype "passive"))
      (node (ref "GENERIC-POWER-18") (pin "0") (pinfunction "1_0") (pintype "passive"))
      (node (ref "U601") (pin "0") (pinfunction "AGND_11_0") (pintype "passive"))
    )
    (net (code "24") (name "Net-(C628-1)") (class "Default")
      (node (ref "C628") (pin "0") (pinfunction "1_0") (pintype "passive"))
      (node (ref "C629") (pin "0") (pinfunction "1_0") (pintype "passive"))
      (node (ref "C630") (pin "0") (pinfunction "1_0") (pintype "passive"))
      (node (ref "C631") (pin "0") (pinfunction "1_0") (pintype "passive"))
      (node (ref "C632") (pin "0") (pinfunction "1_0") (pintype "passive"))
      (node (ref "C633") (pin "0") (pinfunction "1_0") (pintype "passive"))
      (node (ref "C634") (pin "0") (pinfunction "1_0") (pintype "passive"))
      (node (ref "C635") (pin "0") (pinfunction "1_0") (pintype "passive"))
      (node (ref "C636") (pin "0") (pinfunction "1_0") (pintype "passive"))
      (node (ref "C637") (pin "0") (pinfunction "1_0") (pintype "passive"))
      (node (ref "C638") (pin "0") (pinfunction "1_0") (pintype "passive"))
      (node (ref "C639") (pin "0") (pinfunction "1_0") (pintype "passive"))
      (node (ref "C640") (pin "0") (pinfunction "1_0") (pintype "passive"))
      (node (ref "C641") (pin "0") (pinfunction "1_0") (pintype "passive"))
      (node (ref "C642") (pin "0") (pinfunction "1_0") (pintype "passive"))
      (node (ref "C643") (pin "0") (pinfunction "1_0") (pintype "passive"))
      (node (ref "C644") (pin "0") (pinfunction "1_0") (pintype "passive"))
      (node (ref "C645") (pin "0") (pinfunction "1_0") (pintype "passive"))
      (node (ref "GENERIC-POWER-20") (pin "0") (pinfunction "1_0") (pintype "passive"))
      (node (ref "U602") (pin "0") (pinfunction "AVDD_15_0") (pintype "passive"))
    )
    (net (code "25") (name "Net-(C628-2)") (class "Default")
      (node (ref "C628") (pin "0") (pinfunction "2_0") (pintype "passive"))
      (node (ref "C629") (pin "0") (pinfunction "2_0") (pintype "passive"))
      (node (ref "C630") (pin "0") (pinfunction "2_0") (pintype "passive"))
      (node (ref "C631") (pin "0") (pinfunction "2_0") (pintype "passive"))
      (node (ref "C632") (pin "0") (pinfunction "2_0") (pintype "passive"))
      (node (ref "C633") (pin "0") (pinfunction "2_0") (pintype "passive"))
      (node (ref "C634") (pin "0") (pinfunction "2_0") (pintype "passive"))
      (node (ref "C635") (pin "0") (pinfunction "2_0") (pintype "passive"))
      (node (ref "C636") (pin "0") (pinfunction "2_0") (pintype "passive"))
      (node (ref "C637") (pin "0") (pinfunction "2_0") (pintype "passive"))
      (node (ref "C638") (pin "0") (pinfunction "2_0") (pintype "passive"))
      (node (ref "C639") (pin "0") (pinfunction "2_0") (pintype "passive"))
      (node (ref "C640") (pin "0") (pinfunction "2_0") (pintype "passive"))
      (node (ref "C641") (pin "0") (pinfunction "2_0") (pintype "passive"))
      (node (ref "C642") (pin "0") (pinfunction "2_0") (pintype "passive"))
      (node (ref "C643") (pin "0") (pinfunction "2_0") (pintype "passive"))
      (node (ref "C644") (pin "0") (pinfunction "2_0") (pintype "passive"))
      (node (ref "C645") (pin "0") (pinfunction "2_0") (pintype "passive"))
      (node (ref "GENERIC-POWER-22") (pin "0") (pinfunction "1_0") (pintype "passive"))
      (node (ref "U602") (pin "0") (pinfunction "AGND_11_0") (pintype "passive"))
    )
    (net (code "26") (name "Net-(C901-1)") (class "Default")
      (node (ref "C901") (pin "0") (pinfunction "1_0") (pintype "passive"))
      (node (ref "C902") (pin "0") (pinfunction "1_0") (pintype "passive"))
      (node (ref "C905") (pin "0") (pinfunction "+_0") (pintype "passive"))
      (node (ref "GENERIC-POWER-24") (pin "0") (pinfunction "1_0") (pintype "passive"))
      (node (ref "L402") (pin "0") (pinfunction "2_0") (pintype "passive"))
    )
    (net (code "27") (name "Net-(C901-2)") (class "Default")
      (node (ref "C901") (pin "0") (pinfunction "2_0") (pintype "passive"))
      (node (ref "C902") (pin "0") (pinfunction "2_0") (pintype "passive"))
      (node (ref "C903") (pin "0") (pinfunction "2_0") (pintype "passive"))
      (node (ref "C904") (pin "0") (pinfunction "2_0") (pintype "passive"))
      (node (ref "C905") (pin "0") (pinfunction "-_0") (pintype "passive"))
      (node (ref "GND-1-25") (pin "0") (pinfunction "1_0") (pintype "passive"))
    )
    (net (code "28") (name "Net-(C903-1)") (class "Default")
      (node (ref "C903") (pin "0") (pinfunction "1_0") (pintype "passive"))
      (node (ref "C904") (pin "0") (pinfunction "1_0") (pintype "passive"))
      (node (ref "GENERIC-POWER-23") (pin "0") (pinfunction "1_0") (pintype "passive"))
      (node (ref "L402") (pin "0") (pinfunction "1_0") (pintype "passive"))
    )
    (net (code "29") (name "Net-(C1020-1)") (class "Default")
      (node (ref "C1020") (pin "0") (pinfunction "1_0") (pintype "passive"))
      (node (ref "C502") (pin "0") (pinfunction "+_0") (pintype "passive"))
      (node (ref "C510") (pin "0") (pinfunction "1_0") (pintype "passive"))
      (node (ref "D7") (pin "0") (pinfunction "2_0") (pintype "passive"))
      (node (ref "F501") (pin "0") (pinfunction "2_0") (pintype "passive"))
      (node (ref "GENERIC-POWER-0") (pin "0") (pinfunction "1_0") (pintype "passive"))
      (node (ref "R7") (pin "0") (pinfunction "2_0") (pintype "passive"))
      (node (ref "U502") (pin "0") (pinfunction "VIN_0") (pintype "passive"))
    )
    (net (code "30") (name "Net-(C1020-2)") (class "Default")
      (node (ref "C1020") (pin "0") (pinfunction "2_0") (pintype "passive"))
      (node (ref "C502") (pin "0") (pinfunction "-_0") (pintype "passive"))
      (node (ref "C505") (pin "0") (pinfunction "2_0") (pintype "passive"))
      (node (ref "C507") (pin "0") (pinfunction "-_0") (pintype "passive"))
      (node (ref "C508") (pin "0") (pinfunction "-_0") (pintype "passive"))
      (node (ref "C510") (pin "0") (pinfunction "2_0") (pintype "passive"))
      (node (ref "C512") (pin "0") (pinfunction "2_0") (pintype "passive"))
      (node (ref "C513") (pin "0") (pinfunction "2_0") (pintype "passive"))
      (node (ref "C514") (pin "0") (pinfunction "2_0") (pintype "passive"))
      (node (ref "C518") (pin "0") (pinfunction "2_0") (pintype "passive"))
      (node (ref "C519") (pin "0") (pinfunction "2_0") (pintype "passive"))
      (node (ref "GND-1") (pin "0") (pinfunction "1_0") (pintype "passive"))
      (node (ref "J502") (pin "0") (pinfunction "3_0") (pintype "passive"))
      (node (ref "U502") (pin "0") (pinfunction "GND_0") (pintype "passive"))
      (node (ref "U503") (pin "0") (pinfunction "GND_0") (pintype "passive"))
    )
    (net (code "31") (name "Net-(D7-1)") (class "Default")
      (node (ref "D7") (pin "0") (pinfunction "1_0") (pintype "passive"))
      (node (ref "J3") (pin "0") (pinfunction "1_0") (pintype "passive"))
      (node (ref "R7") (pin "0") (pinfunction "1_0") (pintype "passive"))
    )
    (net (code "32") (name "Net-(F501-1)") (class "Default")
      (node (ref "F501") (pin "0") (pinfunction "1_0") (pintype "passive"))
      (node (ref "J502") (pin "0") (pinfunction "1_0") (pintype "passive"))
    )
    (net (code "33") (name "Net-(GND-1-26-1)") (class "Default")
      (node (ref "GND-1-26") (pin "0") (pinfunction "1_0") (pintype "passive"))
      (node (ref "J3") (pin "0") (pinfunction "2_0") (pintype "passive"))
    )
    (net (code "34") (name "Net-(R503-1)") (class "Default")
      (node (ref "R503") (pin "0") (pinfunction "1_0") (pintype "passive"))
      (node (ref "U503") (pin "0") (pinfunction "_RESET_/PG_0") (pintype "passive"))
    )
    (net (code "35") (name "unconnected-(U503-FB{slash}NC-Pad0)") (class "Default")
      (node (ref "U503") (pin "0") (pinfunction "FB/NC_0") (pintype "passive"))
    )
    (net (code "36") (name "unconnected-(U503-NC-Pad0)") (class "Default")
      (node (ref "U503") (pin "0") (pinfunction "NC_0") (pintype "passive"))
    )
    (net (code "37") (name "unconnected-(U503-NC_2-Pad0)") (class "Default")
      (node (ref "U503") (pin "0") (pinfunction "NC_2_0") (pintype "passive"))
    )
    (net (code "38") (name "unconnected-(U503-NC_3-Pad0)") (class "Default")
      (node (ref "U503") (pin "0") (pinfunction "NC_3_0") (pintype "passive"))
    )
    (net (code "39") (name "unconnected-(U503-NC_4-Pad0)") (class "Default")
      (node (ref "U503") (pin "0") (pinfunction "NC_4_0") (pintype "passive"))
    )
  )
)
